# Diode_Drivers.net
KiCad netlist of a schematic drawn in Altium Designer
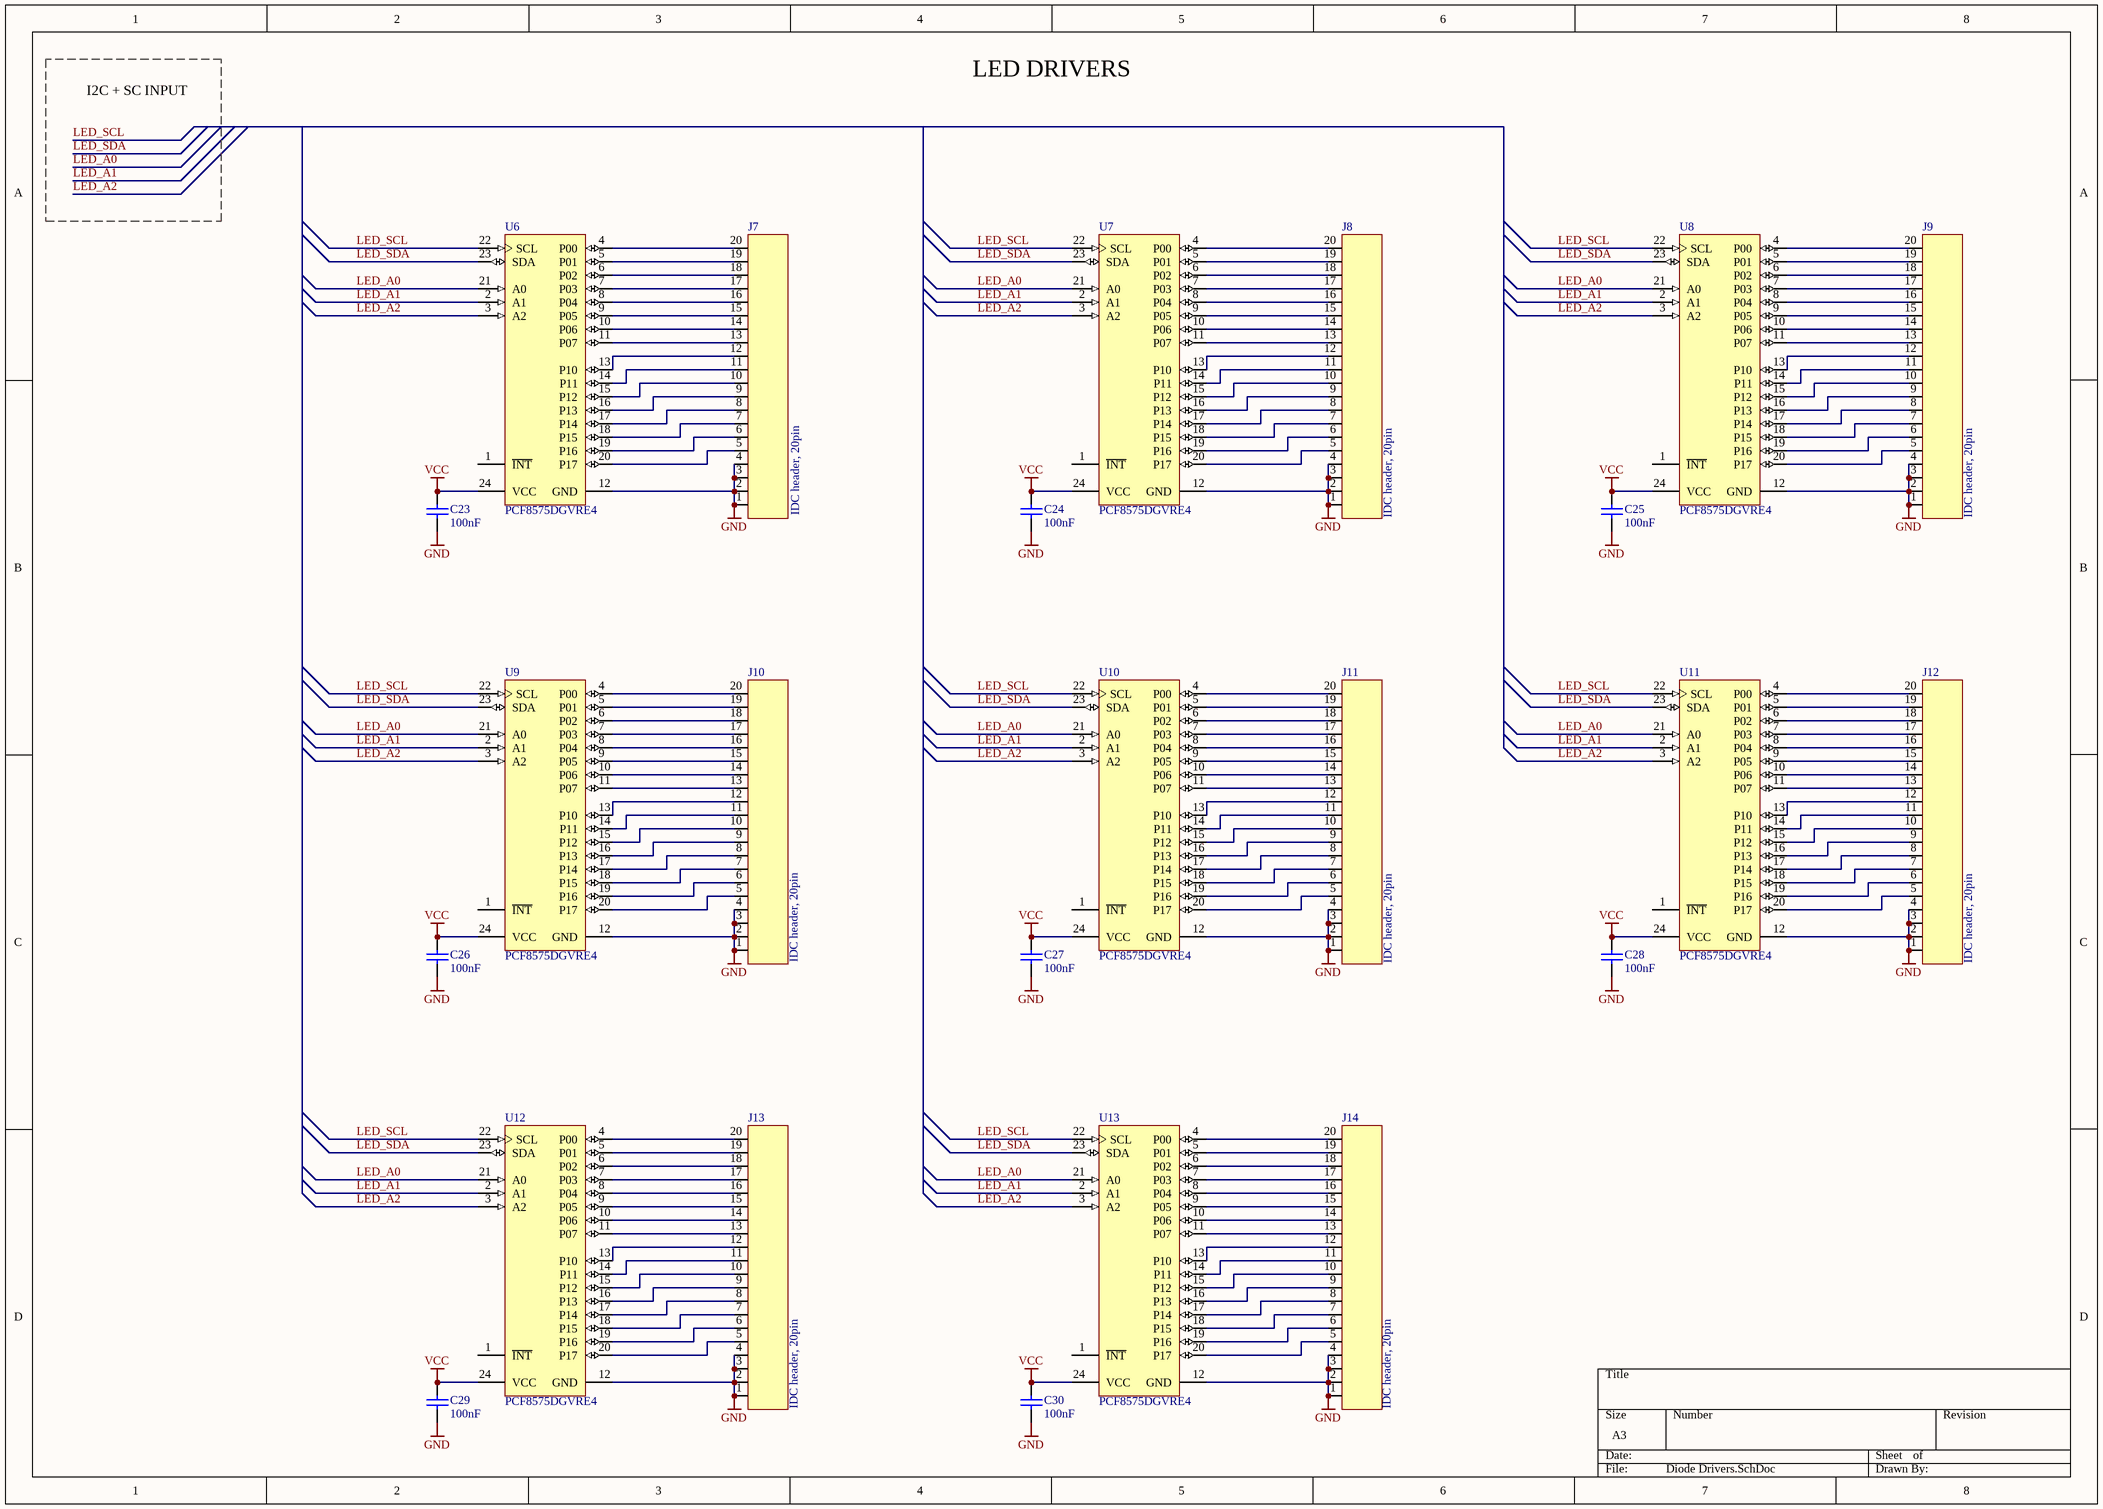
[diagram p0: Diode Drivers.SchDoc]

(export (version "E")
  (design (tool "Eeschema 10.0.6"))
  (components
    (comp (ref "C23")
      (value "100nF")
      (footprint "CAPC0603(1608)100_N")
      (description "CAP 100nF 25V ±20% 0603 (1608 Metric) Thickness 1mm SMD")
      (fields (field (name "TOLERANCE") "Â±20%") (field (name "Comment") "CAP 100nF 25V 0603(1608)"))
      (libsource (lib "Altium Content Vault") (part "CMP-1035-02589-1"))
    )
    (comp (ref "C24")
      (value "100nF")
      (footprint "CAPC0603(1608)100_N")
      (description "CAP 100nF 25V ±20% 0603 (1608 Metric) Thickness 1mm SMD")
      (fields (field (name "TOLERANCE") "Â±20%") (field (name "Comment") "CAP 100nF 25V 0603(1608)"))
      (libsource (lib "Altium Content Vault") (part "CMP-1035-02589-1"))
    )
    (comp (ref "C25")
      (value "100nF")
      (footprint "CAPC0603(1608)100_N")
      (description "CAP 100nF 25V ±20% 0603 (1608 Metric) Thickness 1mm SMD")
      (fields (field (name "TOLERANCE") "Â±20%") (field (name "Comment") "CAP 100nF 25V 0603(1608)"))
      (libsource (lib "Altium Content Vault") (part "CMP-1035-02589-1"))
    )
    (comp (ref "C26")
      (value "100nF")
      (footprint "CAPC0603(1608)100_N")
      (description "CAP 100nF 25V ±20% 0603 (1608 Metric) Thickness 1mm SMD")
      (fields (field (name "TOLERANCE") "Â±20%") (field (name "Comment") "CAP 100nF 25V 0603(1608)"))
      (libsource (lib "Altium Content Vault") (part "CMP-1035-02589-1"))
    )
    (comp (ref "C27")
      (value "100nF")
      (footprint "CAPC0603(1608)100_N")
      (description "CAP 100nF 25V ±20% 0603 (1608 Metric) Thickness 1mm SMD")
      (fields (field (name "TOLERANCE") "Â±20%") (field (name "Comment") "CAP 100nF 25V 0603(1608)"))
      (libsource (lib "Altium Content Vault") (part "CMP-1035-02589-1"))
    )
    (comp (ref "C28")
      (value "100nF")
      (footprint "CAPC0603(1608)100_N")
      (description "CAP 100nF 25V ±20% 0603 (1608 Metric) Thickness 1mm SMD")
      (fields (field (name "TOLERANCE") "Â±20%") (field (name "Comment") "CAP 100nF 25V 0603(1608)"))
      (libsource (lib "Altium Content Vault") (part "CMP-1035-02589-1"))
    )
    (comp (ref "C29")
      (value "100nF")
      (footprint "CAPC0603(1608)100_N")
      (description "CAP 100nF 25V ±20% 0603 (1608 Metric) Thickness 1mm SMD")
      (fields (field (name "TOLERANCE") "Â±20%") (field (name "Comment") "CAP 100nF 25V 0603(1608)"))
      (libsource (lib "Altium Content Vault") (part "CMP-1035-02589-1"))
    )
    (comp (ref "C30")
      (value "100nF")
      (footprint "CAPC0603(1608)100_N")
      (description "CAP 100nF 25V ±20% 0603 (1608 Metric) Thickness 1mm SMD")
      (fields (field (name "TOLERANCE") "Â±20%") (field (name "Comment") "CAP 100nF 25V 0603(1608)"))
      (libsource (lib "Altium Content Vault") (part "CMP-1035-02589-1"))
    )
    (comp (ref "J7")
      (value "IDC header, 20pin")
      (footprint "PKG_ZL231-20PG_R2.54-V")
      (description "Złącze IDC, męskie, proste, 20 pinów, na PCB")
      (libsource (lib "J") (part "J_ZL231-20PG_1"))
    )
    (comp (ref "J8")
      (value "IDC header, 20pin")
      (footprint "PKG_ZL231-20PG_R2.54-V")
      (description "Złącze IDC, męskie, proste, 20 pinów, na PCB")
      (libsource (lib "J") (part "J_ZL231-20PG_1"))
    )
    (comp (ref "J9")
      (value "IDC header, 20pin")
      (footprint "PKG_ZL231-20PG_R2.54-V")
      (libsource (lib "J") (part "J_ZL231-20PG_1"))
    )
    (comp (ref "J10")
      (value "IDC header, 20pin")
      (footprint "PKG_ZL231-20PG_R2.54-V")
      (description "Złącze IDC, męskie, proste, 20 pinów, na PCB")
      (libsource (lib "J") (part "J_ZL231-20PG_1"))
    )
    (comp (ref "J11")
      (value "IDC header, 20pin")
      (footprint "PKG_ZL231-20PG_R2.54-V")
      (description "Złącze IDC, męskie, proste, 20 pinów, na PCB")
      (libsource (lib "J") (part "J_ZL231-20PG_1"))
    )
    (comp (ref "J12")
      (value "IDC header, 20pin")
      (footprint "PKG_ZL231-20PG_R2.54-V")
      (description "Złącze IDC, męskie, proste, 20 pinów, na PCB")
      (libsource (lib "J") (part "J_ZL231-20PG_1"))
    )
    (comp (ref "J13")
      (value "IDC header, 20pin")
      (footprint "PKG_ZL231-20PG_R2.54-V")
      (description "Złącze IDC, męskie, proste, 20 pinów, na PCB")
      (libsource (lib "J") (part "J_ZL231-20PG_1"))
    )
    (comp (ref "J14")
      (value "IDC header, 20pin")
      (footprint "PKG_ZL231-20PG_R2.54-V")
      (description "Złącze IDC, męskie, proste, 20 pinów, na PCB")
      (libsource (lib "J") (part "J_ZL231-20PG_1"))
    )
    (comp (ref "U6")
      (value "PCF8575DGVRE4")
      (footprint "DGV24_M")
      (fields (field (name "MANUFACTURER") "Texas Instruments"))
      (libsource (lib "Altium Content Vault") (part "CMP-0314-00413-1"))
    )
    (comp (ref "U7")
      (value "PCF8575DGVRE4")
      (footprint "DGV24_M")
      (fields (field (name "MANUFACTURER") "Texas Instruments"))
      (libsource (lib "Altium Content Vault") (part "TI-PCF8575-TVSOP_DGV-24"))
    )
    (comp (ref "U8")
      (value "PCF8575DGVRE4")
      (footprint "DGV24_M")
      (fields (field (name "MANUFACTURER") "Texas Instruments"))
      (libsource (lib "Altium Content Vault") (part "TI-PCF8575-TVSOP_DGV-24"))
    )
    (comp (ref "U9")
      (value "PCF8575DGVRE4")
      (footprint "DGV24_M")
      (fields (field (name "MANUFACTURER") "Texas Instruments"))
      (libsource (lib "Altium Content Vault") (part "CMP-0314-00413-1"))
    )
    (comp (ref "U10")
      (value "PCF8575DGVRE4")
      (footprint "DGV24_M")
      (fields (field (name "MANUFACTURER") "Texas Instruments"))
      (libsource (lib "Altium Content Vault") (part "TI-PCF8575-TVSOP_DGV-24"))
    )
    (comp (ref "U11")
      (value "PCF8575DGVRE4")
      (footprint "DGV24_M")
      (fields (field (name "MANUFACTURER") "Texas Instruments"))
      (libsource (lib "Altium Content Vault") (part "TI-PCF8575-TVSOP_DGV-24"))
    )
    (comp (ref "U12")
      (value "PCF8575DGVRE4")
      (footprint "DGV24_M")
      (fields (field (name "MANUFACTURER") "Texas Instruments"))
      (libsource (lib "Altium Content Vault") (part "TI-PCF8575-TVSOP_DGV-24"))
    )
    (comp (ref "U13")
      (value "PCF8575DGVRE4")
      (footprint "DGV24_M")
      (fields (field (name "MANUFACTURER") "Texas Instruments"))
      (libsource (lib "Altium Content Vault") (part "TI-PCF8575-TVSOP_DGV-24"))
    )
  )
  (nets
    (net (code "1") (name "/LED_A0") (class "Default")
      (node (ref "U10") (pin "21") (pinfunction "A0_21") (pintype "input"))
      (node (ref "U11") (pin "21") (pinfunction "A0_21") (pintype "input"))
      (node (ref "U12") (pin "21") (pinfunction "A0_21") (pintype "input"))
      (node (ref "U13") (pin "21") (pinfunction "A0_21") (pintype "input"))
      (node (ref "U6") (pin "21") (pinfunction "A0_21") (pintype "input"))
      (node (ref "U7") (pin "21") (pinfunction "A0_21") (pintype "input"))
      (node (ref "U8") (pin "21") (pinfunction "A0_21") (pintype "input"))
      (node (ref "U9") (pin "21") (pinfunction "A0_21") (pintype "input"))
    )
    (net (code "2") (name "/LED_A1") (class "Default")
      (node (ref "U10") (pin "2") (pinfunction "A1_2") (pintype "input"))
      (node (ref "U11") (pin "2") (pinfunction "A1_2") (pintype "input"))
      (node (ref "U12") (pin "2") (pinfunction "A1_2") (pintype "input"))
      (node (ref "U13") (pin "2") (pinfunction "A1_2") (pintype "input"))
      (node (ref "U6") (pin "2") (pinfunction "A1_2") (pintype "input"))
      (node (ref "U7") (pin "2") (pinfunction "A1_2") (pintype "input"))
      (node (ref "U8") (pin "2") (pinfunction "A1_2") (pintype "input"))
      (node (ref "U9") (pin "2") (pinfunction "A1_2") (pintype "input"))
    )
    (net (code "3") (name "/LED_A2") (class "Default")
      (node (ref "U10") (pin "3") (pinfunction "A2_3") (pintype "input"))
      (node (ref "U11") (pin "3") (pinfunction "A2_3") (pintype "input"))
      (node (ref "U12") (pin "3") (pinfunction "A2_3") (pintype "input"))
      (node (ref "U13") (pin "3") (pinfunction "A2_3") (pintype "input"))
      (node (ref "U6") (pin "3") (pinfunction "A2_3") (pintype "input"))
      (node (ref "U7") (pin "3") (pinfunction "A2_3") (pintype "input"))
      (node (ref "U8") (pin "3") (pinfunction "A2_3") (pintype "input"))
      (node (ref "U9") (pin "3") (pinfunction "A2_3") (pintype "input"))
    )
    (net (code "4") (name "/LED_SCL") (class "Default")
      (node (ref "U10") (pin "22") (pinfunction "SCL_22") (pintype "input"))
      (node (ref "U11") (pin "22") (pinfunction "SCL_22") (pintype "input"))
      (node (ref "U12") (pin "22") (pinfunction "SCL_22") (pintype "input"))
      (node (ref "U13") (pin "22") (pinfunction "SCL_22") (pintype "input"))
      (node (ref "U6") (pin "22") (pinfunction "SCL_22") (pintype "input"))
      (node (ref "U7") (pin "22") (pinfunction "SCL_22") (pintype "input"))
      (node (ref "U8") (pin "22") (pinfunction "SCL_22") (pintype "input"))
      (node (ref "U9") (pin "22") (pinfunction "SCL_22") (pintype "input"))
    )
    (net (code "5") (name "/LED_SDA") (class "Default")
      (node (ref "U10") (pin "23") (pinfunction "SDA_23") (pintype "bidirectional"))
      (node (ref "U11") (pin "23") (pinfunction "SDA_23") (pintype "bidirectional"))
      (node (ref "U12") (pin "23") (pinfunction "SDA_23") (pintype "bidirectional"))
      (node (ref "U13") (pin "23") (pinfunction "SDA_23") (pintype "bidirectional"))
      (node (ref "U6") (pin "23") (pinfunction "SDA_23") (pintype "bidirectional"))
      (node (ref "U7") (pin "23") (pinfunction "SDA_23") (pintype "bidirectional"))
      (node (ref "U8") (pin "23") (pinfunction "SDA_23") (pintype "bidirectional"))
      (node (ref "U9") (pin "23") (pinfunction "SDA_23") (pintype "bidirectional"))
    )
    (net (code "6") (name "GND") (class "Default")
      (node (ref "C23") (pin "2") (pinfunction "2_2") (pintype "passive"))
      (node (ref "C24") (pin "2") (pinfunction "2_2") (pintype "passive"))
      (node (ref "C25") (pin "2") (pinfunction "2_2") (pintype "passive"))
      (node (ref "C26") (pin "2") (pinfunction "2_2") (pintype "passive"))
      (node (ref "C27") (pin "2") (pinfunction "2_2") (pintype "passive"))
      (node (ref "C28") (pin "2") (pinfunction "2_2") (pintype "passive"))
      (node (ref "C29") (pin "2") (pinfunction "2_2") (pintype "passive"))
      (node (ref "C30") (pin "2") (pinfunction "2_2") (pintype "passive"))
      (node (ref "J10") (pin "1") (pinfunction "1_1") (pintype "passive"))
      (node (ref "J10") (pin "2") (pinfunction "2_2") (pintype "passive"))
      (node (ref "J10") (pin "3") (pinfunction "3_3") (pintype "passive"))
      (node (ref "J10") (pin "4") (pinfunction "4_4") (pintype "passive"))
      (node (ref "J11") (pin "1") (pinfunction "1_1") (pintype "passive"))
      (node (ref "J11") (pin "2") (pinfunction "2_2") (pintype "passive"))
      (node (ref "J11") (pin "3") (pinfunction "3_3") (pintype "passive"))
      (node (ref "J11") (pin "4") (pinfunction "4_4") (pintype "passive"))
      (node (ref "J12") (pin "1") (pinfunction "1_1") (pintype "passive"))
      (node (ref "J12") (pin "2") (pinfunction "2_2") (pintype "passive"))
      (node (ref "J12") (pin "3") (pinfunction "3_3") (pintype "passive"))
      (node (ref "J12") (pin "4") (pinfunction "4_4") (pintype "passive"))
      (node (ref "J13") (pin "1") (pinfunction "1_1") (pintype "passive"))
      (node (ref "J13") (pin "2") (pinfunction "2_2") (pintype "passive"))
      (node (ref "J13") (pin "3") (pinfunction "3_3") (pintype "passive"))
      (node (ref "J13") (pin "4") (pinfunction "4_4") (pintype "passive"))
      (node (ref "J14") (pin "1") (pinfunction "1_1") (pintype "passive"))
      (node (ref "J14") (pin "2") (pinfunction "2_2") (pintype "passive"))
      (node (ref "J14") (pin "3") (pinfunction "3_3") (pintype "passive"))
      (node (ref "J14") (pin "4") (pinfunction "4_4") (pintype "passive"))
      (node (ref "J7") (pin "1") (pinfunction "1_1") (pintype "passive"))
      (node (ref "J7") (pin "2") (pinfunction "2_2") (pintype "passive"))
      (node (ref "J7") (pin "3") (pinfunction "3_3") (pintype "passive"))
      (node (ref "J7") (pin "4") (pinfunction "4_4") (pintype "passive"))
      (node (ref "J8") (pin "1") (pinfunction "1_1") (pintype "passive"))
      (node (ref "J8") (pin "2") (pinfunction "2_2") (pintype "passive"))
      (node (ref "J8") (pin "3") (pinfunction "3_3") (pintype "passive"))
      (node (ref "J8") (pin "4") (pinfunction "4_4") (pintype "passive"))
      (node (ref "J9") (pin "1") (pinfunction "1_1") (pintype "passive"))
      (node (ref "J9") (pin "2") (pinfunction "2_2") (pintype "passive"))
      (node (ref "J9") (pin "3") (pinfunction "3_3") (pintype "passive"))
      (node (ref "J9") (pin "4") (pinfunction "4_4") (pintype "passive"))
      (node (ref "U10") (pin "12") (pinfunction "GND_12") (pintype "power_in"))
      (node (ref "U11") (pin "12") (pinfunction "GND_12") (pintype "power_in"))
      (node (ref "U12") (pin "12") (pinfunction "GND_12") (pintype "power_in"))
      (node (ref "U13") (pin "12") (pinfunction "GND_12") (pintype "power_in"))
      (node (ref "U6") (pin "12") (pinfunction "GND_12") (pintype "power_in"))
      (node (ref "U7") (pin "12") (pinfunction "GND_12") (pintype "power_in"))
      (node (ref "U8") (pin "12") (pinfunction "GND_12") (pintype "power_in"))
      (node (ref "U9") (pin "12") (pinfunction "GND_12") (pintype "power_in"))
    )
    (net (code "7") (name "Net-(U6-P00)") (class "Default")
      (node (ref "J7") (pin "20") (pinfunction "20_20") (pintype "passive"))
      (node (ref "U6") (pin "4") (pinfunction "P00_4") (pintype "bidirectional"))
    )
    (net (code "8") (name "Net-(U6-P01)") (class "Default")
      (node (ref "J7") (pin "19") (pinfunction "19_19") (pintype "passive"))
      (node (ref "U6") (pin "5") (pinfunction "P01_5") (pintype "bidirectional"))
    )
    (net (code "9") (name "Net-(U6-P02)") (class "Default")
      (node (ref "J7") (pin "18") (pinfunction "18_18") (pintype "passive"))
      (node (ref "U6") (pin "6") (pinfunction "P02_6") (pintype "bidirectional"))
    )
    (net (code "10") (name "Net-(U6-P03)") (class "Default")
      (node (ref "J7") (pin "17") (pinfunction "17_17") (pintype "passive"))
      (node (ref "U6") (pin "7") (pinfunction "P03_7") (pintype "bidirectional"))
    )
    (net (code "11") (name "Net-(U6-P04)") (class "Default")
      (node (ref "J7") (pin "16") (pinfunction "16_16") (pintype "passive"))
      (node (ref "U6") (pin "8") (pinfunction "P04_8") (pintype "bidirectional"))
    )
    (net (code "12") (name "Net-(U6-P05)") (class "Default")
      (node (ref "J7") (pin "15") (pinfunction "15_15") (pintype "passive"))
      (node (ref "U6") (pin "9") (pinfunction "P05_9") (pintype "bidirectional"))
    )
    (net (code "13") (name "Net-(U6-P06)") (class "Default")
      (node (ref "J7") (pin "14") (pinfunction "14_14") (pintype "passive"))
      (node (ref "U6") (pin "10") (pinfunction "P06_10") (pintype "bidirectional"))
    )
    (net (code "14") (name "Net-(U6-P07)") (class "Default")
      (node (ref "J7") (pin "13") (pinfunction "13_13") (pintype "passive"))
      (node (ref "U6") (pin "11") (pinfunction "P07_11") (pintype "bidirectional"))
    )
    (net (code "15") (name "Net-(U6-P10)") (class "Default")
      (node (ref "J7") (pin "12") (pinfunction "12_12") (pintype "passive"))
      (node (ref "U6") (pin "13") (pinfunction "P10_13") (pintype "bidirectional"))
    )
    (net (code "16") (name "Net-(U6-P11)") (class "Default")
      (node (ref "J7") (pin "11") (pinfunction "11_11") (pintype "passive"))
      (node (ref "U6") (pin "14") (pinfunction "P11_14") (pintype "bidirectional"))
    )
    (net (code "17") (name "Net-(U6-P12)") (class "Default")
      (node (ref "J7") (pin "10") (pinfunction "10_10") (pintype "passive"))
      (node (ref "U6") (pin "15") (pinfunction "P12_15") (pintype "bidirectional"))
    )
    (net (code "18") (name "Net-(U6-P13)") (class "Default")
      (node (ref "J7") (pin "9") (pinfunction "9_9") (pintype "passive"))
      (node (ref "U6") (pin "16") (pinfunction "P13_16") (pintype "bidirectional"))
    )
    (net (code "19") (name "Net-(U6-P14)") (class "Default")
      (node (ref "J7") (pin "8") (pinfunction "8_8") (pintype "passive"))
      (node (ref "U6") (pin "17") (pinfunction "P14_17") (pintype "bidirectional"))
    )
    (net (code "20") (name "Net-(U6-P15)") (class "Default")
      (node (ref "J7") (pin "7") (pinfunction "7_7") (pintype "passive"))
      (node (ref "U6") (pin "18") (pinfunction "P15_18") (pintype "bidirectional"))
    )
    (net (code "21") (name "Net-(U6-P16)") (class "Default")
      (node (ref "J7") (pin "6") (pinfunction "6_6") (pintype "passive"))
      (node (ref "U6") (pin "19") (pinfunction "P16_19") (pintype "bidirectional"))
    )
    (net (code "22") (name "Net-(U6-P17)") (class "Default")
      (node (ref "J7") (pin "5") (pinfunction "5_5") (pintype "passive"))
      (node (ref "U6") (pin "20") (pinfunction "P17_20") (pintype "bidirectional"))
    )
    (net (code "23") (name "Net-(U7-P00)") (class "Default")
      (node (ref "J8") (pin "20") (pinfunction "20_20") (pintype "passive"))
      (node (ref "U7") (pin "4") (pinfunction "P00_4") (pintype "bidirectional"))
    )
    (net (code "24") (name "Net-(U7-P01)") (class "Default")
      (node (ref "J8") (pin "19") (pinfunction "19_19") (pintype "passive"))
      (node (ref "U7") (pin "5") (pinfunction "P01_5") (pintype "bidirectional"))
    )
    (net (code "25") (name "Net-(U7-P02)") (class "Default")
      (node (ref "J8") (pin "18") (pinfunction "18_18") (pintype "passive"))
      (node (ref "U7") (pin "6") (pinfunction "P02_6") (pintype "bidirectional"))
    )
    (net (code "26") (name "Net-(U7-P03)") (class "Default")
      (node (ref "J8") (pin "17") (pinfunction "17_17") (pintype "passive"))
      (node (ref "U7") (pin "7") (pinfunction "P03_7") (pintype "bidirectional"))
    )
    (net (code "27") (name "Net-(U7-P04)") (class "Default")
      (node (ref "J8") (pin "16") (pinfunction "16_16") (pintype "passive"))
      (node (ref "U7") (pin "8") (pinfunction "P04_8") (pintype "bidirectional"))
    )
    (net (code "28") (name "Net-(U7-P05)") (class "Default")
      (node (ref "J8") (pin "15") (pinfunction "15_15") (pintype "passive"))
      (node (ref "U7") (pin "9") (pinfunction "P05_9") (pintype "bidirectional"))
    )
    (net (code "29") (name "Net-(U7-P06)") (class "Default")
      (node (ref "J8") (pin "14") (pinfunction "14_14") (pintype "passive"))
      (node (ref "U7") (pin "10") (pinfunction "P06_10") (pintype "bidirectional"))
    )
    (net (code "30") (name "Net-(U7-P07)") (class "Default")
      (node (ref "J8") (pin "13") (pinfunction "13_13") (pintype "passive"))
      (node (ref "U7") (pin "11") (pinfunction "P07_11") (pintype "bidirectional"))
    )
    (net (code "31") (name "Net-(U7-P10)") (class "Default")
      (node (ref "J8") (pin "12") (pinfunction "12_12") (pintype "passive"))
      (node (ref "U7") (pin "13") (pinfunction "P10_13") (pintype "bidirectional"))
    )
    (net (code "32") (name "Net-(U7-P11)") (class "Default")
      (node (ref "J8") (pin "11") (pinfunction "11_11") (pintype "passive"))
      (node (ref "U7") (pin "14") (pinfunction "P11_14") (pintype "bidirectional"))
    )
    (net (code "33") (name "Net-(U7-P12)") (class "Default")
      (node (ref "J8") (pin "10") (pinfunction "10_10") (pintype "passive"))
      (node (ref "U7") (pin "15") (pinfunction "P12_15") (pintype "bidirectional"))
    )
    (net (code "34") (name "Net-(U7-P13)") (class "Default")
      (node (ref "J8") (pin "9") (pinfunction "9_9") (pintype "passive"))
      (node (ref "U7") (pin "16") (pinfunction "P13_16") (pintype "bidirectional"))
    )
    (net (code "35") (name "Net-(U7-P14)") (class "Default")
      (node (ref "J8") (pin "8") (pinfunction "8_8") (pintype "passive"))
      (node (ref "U7") (pin "17") (pinfunction "P14_17") (pintype "bidirectional"))
    )
    (net (code "36") (name "Net-(U7-P15)") (class "Default")
      (node (ref "J8") (pin "7") (pinfunction "7_7") (pintype "passive"))
      (node (ref "U7") (pin "18") (pinfunction "P15_18") (pintype "bidirectional"))
    )
    (net (code "37") (name "Net-(U7-P16)") (class "Default")
      (node (ref "J8") (pin "6") (pinfunction "6_6") (pintype "passive"))
      (node (ref "U7") (pin "19") (pinfunction "P16_19") (pintype "bidirectional"))
    )
    (net (code "38") (name "Net-(U7-P17)") (class "Default")
      (node (ref "J8") (pin "5") (pinfunction "5_5") (pintype "passive"))
      (node (ref "U7") (pin "20") (pinfunction "P17_20") (pintype "bidirectional"))
    )
    (net (code "39") (name "Net-(U8-P00)") (class "Default")
      (node (ref "J9") (pin "20") (pinfunction "20_20") (pintype "passive"))
      (node (ref "U8") (pin "4") (pinfunction "P00_4") (pintype "bidirectional"))
    )
    (net (code "40") (name "Net-(U8-P01)") (class "Default")
      (node (ref "J9") (pin "19") (pinfunction "19_19") (pintype "passive"))
      (node (ref "U8") (pin "5") (pinfunction "P01_5") (pintype "bidirectional"))
    )
    (net (code "41") (name "Net-(U8-P02)") (class "Default")
      (node (ref "J9") (pin "18") (pinfunction "18_18") (pintype "passive"))
      (node (ref "U8") (pin "6") (pinfunction "P02_6") (pintype "bidirectional"))
    )
    (net (code "42") (name "Net-(U8-P03)") (class "Default")
      (node (ref "J9") (pin "17") (pinfunction "17_17") (pintype "passive"))
      (node (ref "U8") (pin "7") (pinfunction "P03_7") (pintype "bidirectional"))
    )
    (net (code "43") (name "Net-(U8-P04)") (class "Default")
      (node (ref "J9") (pin "16") (pinfunction "16_16") (pintype "passive"))
      (node (ref "U8") (pin "8") (pinfunction "P04_8") (pintype "bidirectional"))
    )
    (net (code "44") (name "Net-(U8-P05)") (class "Default")
      (node (ref "J9") (pin "15") (pinfunction "15_15") (pintype "passive"))
      (node (ref "U8") (pin "9") (pinfunction "P05_9") (pintype "bidirectional"))
    )
    (net (code "45") (name "Net-(U8-P06)") (class "Default")
      (node (ref "J9") (pin "14") (pinfunction "14_14") (pintype "passive"))
      (node (ref "U8") (pin "10") (pinfunction "P06_10") (pintype "bidirectional"))
    )
    (net (code "46") (name "Net-(U8-P07)") (class "Default")
      (node (ref "J9") (pin "13") (pinfunction "13_13") (pintype "passive"))
      (node (ref "U8") (pin "11") (pinfunction "P07_11") (pintype "bidirectional"))
    )
    (net (code "47") (name "Net-(U8-P10)") (class "Default")
      (node (ref "J9") (pin "12") (pinfunction "12_12") (pintype "passive"))
      (node (ref "U8") (pin "13") (pinfunction "P10_13") (pintype "bidirectional"))
    )
    (net (code "48") (name "Net-(U8-P11)") (class "Default")
      (node (ref "J9") (pin "11") (pinfunction "11_11") (pintype "passive"))
      (node (ref "U8") (pin "14") (pinfunction "P11_14") (pintype "bidirectional"))
    )
    (net (code "49") (name "Net-(U8-P12)") (class "Default")
      (node (ref "J9") (pin "10") (pinfunction "10_10") (pintype "passive"))
      (node (ref "U8") (pin "15") (pinfunction "P12_15") (pintype "bidirectional"))
    )
    (net (code "50") (name "Net-(U8-P13)") (class "Default")
      (node (ref "J9") (pin "9") (pinfunction "9_9") (pintype "passive"))
      (node (ref "U8") (pin "16") (pinfunction "P13_16") (pintype "bidirectional"))
    )
    (net (code "51") (name "Net-(U8-P14)") (class "Default")
      (node (ref "J9") (pin "8") (pinfunction "8_8") (pintype "passive"))
      (node (ref "U8") (pin "17") (pinfunction "P14_17") (pintype "bidirectional"))
    )
    (net (code "52") (name "Net-(U8-P15)") (class "Default")
      (node (ref "J9") (pin "7") (pinfunction "7_7") (pintype "passive"))
      (node (ref "U8") (pin "18") (pinfunction "P15_18") (pintype "bidirectional"))
    )
    (net (code "53") (name "Net-(U8-P16)") (class "Default")
      (node (ref "J9") (pin "6") (pinfunction "6_6") (pintype "passive"))
      (node (ref "U8") (pin "19") (pinfunction "P16_19") (pintype "bidirectional"))
    )
    (net (code "54") (name "Net-(U8-P17)") (class "Default")
      (node (ref "J9") (pin "5") (pinfunction "5_5") (pintype "passive"))
      (node (ref "U8") (pin "20") (pinfunction "P17_20") (pintype "bidirectional"))
    )
    (net (code "55") (name "Net-(U9-P00)") (class "Default")
      (node (ref "J10") (pin "20") (pinfunction "20_20") (pintype "passive"))
      (node (ref "U9") (pin "4") (pinfunction "P00_4") (pintype "bidirectional"))
    )
    (net (code "56") (name "Net-(U9-P01)") (class "Default")
      (node (ref "J10") (pin "19") (pinfunction "19_19") (pintype "passive"))
      (node (ref "U9") (pin "5") (pinfunction "P01_5") (pintype "bidirectional"))
    )
    (net (code "57") (name "Net-(U9-P02)") (class "Default")
      (node (ref "J10") (pin "18") (pinfunction "18_18") (pintype "passive"))
      (node (ref "U9") (pin "6") (pinfunction "P02_6") (pintype "bidirectional"))
    )
    (net (code "58") (name "Net-(U9-P03)") (class "Default")
      (node (ref "J10") (pin "17") (pinfunction "17_17") (pintype "passive"))
      (node (ref "U9") (pin "7") (pinfunction "P03_7") (pintype "bidirectional"))
    )
    (net (code "59") (name "Net-(U9-P04)") (class "Default")
      (node (ref "J10") (pin "16") (pinfunction "16_16") (pintype "passive"))
      (node (ref "U9") (pin "8") (pinfunction "P04_8") (pintype "bidirectional"))
    )
    (net (code "60") (name "Net-(U9-P05)") (class "Default")
      (node (ref "J10") (pin "15") (pinfunction "15_15") (pintype "passive"))
      (node (ref "U9") (pin "9") (pinfunction "P05_9") (pintype "bidirectional"))
    )
    (net (code "61") (name "Net-(U9-P06)") (class "Default")
      (node (ref "J10") (pin "14") (pinfunction "14_14") (pintype "passive"))
      (node (ref "U9") (pin "10") (pinfunction "P06_10") (pintype "bidirectional"))
    )
    (net (code "62") (name "Net-(U9-P07)") (class "Default")
      (node (ref "J10") (pin "13") (pinfunction "13_13") (pintype "passive"))
      (node (ref "U9") (pin "11") (pinfunction "P07_11") (pintype "bidirectional"))
    )
    (net (code "63") (name "Net-(U9-P10)") (class "Default")
      (node (ref "J10") (pin "12") (pinfunction "12_12") (pintype "passive"))
      (node (ref "U9") (pin "13") (pinfunction "P10_13") (pintype "bidirectional"))
    )
    (net (code "64") (name "Net-(U9-P11)") (class "Default")
      (node (ref "J10") (pin "11") (pinfunction "11_11") (pintype "passive"))
      (node (ref "U9") (pin "14") (pinfunction "P11_14") (pintype "bidirectional"))
    )
    (net (code "65") (name "Net-(U9-P12)") (class "Default")
      (node (ref "J10") (pin "10") (pinfunction "10_10") (pintype "passive"))
      (node (ref "U9") (pin "15") (pinfunction "P12_15") (pintype "bidirectional"))
    )
    (net (code "66") (name "Net-(U9-P13)") (class "Default")
      (node (ref "J10") (pin "9") (pinfunction "9_9") (pintype "passive"))
      (node (ref "U9") (pin "16") (pinfunction "P13_16") (pintype "bidirectional"))
    )
    (net (code "67") (name "Net-(U9-P14)") (class "Default")
      (node (ref "J10") (pin "8") (pinfunction "8_8") (pintype "passive"))
      (node (ref "U9") (pin "17") (pinfunction "P14_17") (pintype "bidirectional"))
    )
    (net (code "68") (name "Net-(U9-P15)") (class "Default")
      (node (ref "J10") (pin "7") (pinfunction "7_7") (pintype "passive"))
      (node (ref "U9") (pin "18") (pinfunction "P15_18") (pintype "bidirectional"))
    )
    (net (code "69") (name "Net-(U9-P16)") (class "Default")
      (node (ref "J10") (pin "6") (pinfunction "6_6") (pintype "passive"))
      (node (ref "U9") (pin "19") (pinfunction "P16_19") (pintype "bidirectional"))
    )
    (net (code "70") (name "Net-(U9-P17)") (class "Default")
      (node (ref "J10") (pin "5") (pinfunction "5_5") (pintype "passive"))
      (node (ref "U9") (pin "20") (pinfunction "P17_20") (pintype "bidirectional"))
    )
    (net (code "71") (name "Net-(U10-P00)") (class "Default")
      (node (ref "J11") (pin "20") (pinfunction "20_20") (pintype "passive"))
      (node (ref "U10") (pin "4") (pinfunction "P00_4") (pintype "bidirectional"))
    )
    (net (code "72") (name "Net-(U10-P01)") (class "Default")
      (node (ref "J11") (pin "19") (pinfunction "19_19") (pintype "passive"))
      (node (ref "U10") (pin "5") (pinfunction "P01_5") (pintype "bidirectional"))
    )
    (net (code "73") (name "Net-(U10-P02)") (class "Default")
      (node (ref "J11") (pin "18") (pinfunction "18_18") (pintype "passive"))
      (node (ref "U10") (pin "6") (pinfunction "P02_6") (pintype "bidirectional"))
    )
    (net (code "74") (name "Net-(U10-P03)") (class "Default")
      (node (ref "J11") (pin "17") (pinfunction "17_17") (pintype "passive"))
      (node (ref "U10") (pin "7") (pinfunction "P03_7") (pintype "bidirectional"))
    )
    (net (code "75") (name "Net-(U10-P04)") (class "Default")
      (node (ref "J11") (pin "16") (pinfunction "16_16") (pintype "passive"))
      (node (ref "U10") (pin "8") (pinfunction "P04_8") (pintype "bidirectional"))
    )
    (net (code "76") (name "Net-(U10-P05)") (class "Default")
      (node (ref "J11") (pin "15") (pinfunction "15_15") (pintype "passive"))
      (node (ref "U10") (pin "9") (pinfunction "P05_9") (pintype "bidirectional"))
    )
    (net (code "77") (name "Net-(U10-P06)") (class "Default")
      (node (ref "J11") (pin "14") (pinfunction "14_14") (pintype "passive"))
      (node (ref "U10") (pin "10") (pinfunction "P06_10") (pintype "bidirectional"))
    )
    (net (code "78") (name "Net-(U10-P07)") (class "Default")
      (node (ref "J11") (pin "13") (pinfunction "13_13") (pintype "passive"))
      (node (ref "U10") (pin "11") (pinfunction "P07_11") (pintype "bidirectional"))
    )
    (net (code "79") (name "Net-(U10-P10)") (class "Default")
      (node (ref "J11") (pin "12") (pinfunction "12_12") (pintype "passive"))
      (node (ref "U10") (pin "13") (pinfunction "P10_13") (pintype "bidirectional"))
    )
    (net (code "80") (name "Net-(U10-P11)") (class "Default")
      (node (ref "J11") (pin "11") (pinfunction "11_11") (pintype "passive"))
      (node (ref "U10") (pin "14") (pinfunction "P11_14") (pintype "bidirectional"))
    )
    (net (code "81") (name "Net-(U10-P12)") (class "Default")
      (node (ref "J11") (pin "10") (pinfunction "10_10") (pintype "passive"))
      (node (ref "U10") (pin "15") (pinfunction "P12_15") (pintype "bidirectional"))
    )
    (net (code "82") (name "Net-(U10-P13)") (class "Default")
      (node (ref "J11") (pin "9") (pinfunction "9_9") (pintype "passive"))
      (node (ref "U10") (pin "16") (pinfunction "P13_16") (pintype "bidirectional"))
    )
    (net (code "83") (name "Net-(U10-P14)") (class "Default")
      (node (ref "J11") (pin "8") (pinfunction "8_8") (pintype "passive"))
      (node (ref "U10") (pin "17") (pinfunction "P14_17") (pintype "bidirectional"))
    )
    (net (code "84") (name "Net-(U10-P15)") (class "Default")
      (node (ref "J11") (pin "7") (pinfunction "7_7") (pintype "passive"))
      (node (ref "U10") (pin "18") (pinfunction "P15_18") (pintype "bidirectional"))
    )
    (net (code "85") (name "Net-(U10-P16)") (class "Default")
      (node (ref "J11") (pin "6") (pinfunction "6_6") (pintype "passive"))
      (node (ref "U10") (pin "19") (pinfunction "P16_19") (pintype "bidirectional"))
    )
    (net (code "86") (name "Net-(U10-P17)") (class "Default")
      (node (ref "J11") (pin "5") (pinfunction "5_5") (pintype "passive"))
      (node (ref "U10") (pin "20") (pinfunction "P17_20") (pintype "bidirectional"))
    )
    (net (code "87") (name "Net-(U11-P00)") (class "Default")
      (node (ref "J12") (pin "20") (pinfunction "20_20") (pintype "passive"))
      (node (ref "U11") (pin "4") (pinfunction "P00_4") (pintype "bidirectional"))
    )
    (net (code "88") (name "Net-(U11-P01)") (class "Default")
      (node (ref "J12") (pin "19") (pinfunction "19_19") (pintype "passive"))
      (node (ref "U11") (pin "5") (pinfunction "P01_5") (pintype "bidirectional"))
    )
    (net (code "89") (name "Net-(U11-P02)") (class "Default")
      (node (ref "J12") (pin "18") (pinfunction "18_18") (pintype "passive"))
      (node (ref "U11") (pin "6") (pinfunction "P02_6") (pintype "bidirectional"))
    )
    (net (code "90") (name "Net-(U11-P03)") (class "Default")
      (node (ref "J12") (pin "17") (pinfunction "17_17") (pintype "passive"))
      (node (ref "U11") (pin "7") (pinfunction "P03_7") (pintype "bidirectional"))
    )
    (net (code "91") (name "Net-(U11-P04)") (class "Default")
      (node (ref "J12") (pin "16") (pinfunction "16_16") (pintype "passive"))
      (node (ref "U11") (pin "8") (pinfunction "P04_8") (pintype "bidirectional"))
    )
    (net (code "92") (name "Net-(U11-P05)") (class "Default")
      (node (ref "J12") (pin "15") (pinfunction "15_15") (pintype "passive"))
      (node (ref "U11") (pin "9") (pinfunction "P05_9") (pintype "bidirectional"))
    )
    (net (code "93") (name "Net-(U11-P06)") (class "Default")
      (node (ref "J12") (pin "14") (pinfunction "14_14") (pintype "passive"))
      (node (ref "U11") (pin "10") (pinfunction "P06_10") (pintype "bidirectional"))
    )
    (net (code "94") (name "Net-(U11-P07)") (class "Default")
      (node (ref "J12") (pin "13") (pinfunction "13_13") (pintype "passive"))
      (node (ref "U11") (pin "11") (pinfunction "P07_11") (pintype "bidirectional"))
    )
    (net (code "95") (name "Net-(U11-P10)") (class "Default")
      (node (ref "J12") (pin "12") (pinfunction "12_12") (pintype "passive"))
      (node (ref "U11") (pin "13") (pinfunction "P10_13") (pintype "bidirectional"))
    )
    (net (code "96") (name "Net-(U11-P11)") (class "Default")
      (node (ref "J12") (pin "11") (pinfunction "11_11") (pintype "passive"))
      (node (ref "U11") (pin "14") (pinfunction "P11_14") (pintype "bidirectional"))
    )
    (net (code "97") (name "Net-(U11-P12)") (class "Default")
      (node (ref "J12") (pin "10") (pinfunction "10_10") (pintype "passive"))
      (node (ref "U11") (pin "15") (pinfunction "P12_15") (pintype "bidirectional"))
    )
    (net (code "98") (name "Net-(U11-P13)") (class "Default")
      (node (ref "J12") (pin "9") (pinfunction "9_9") (pintype "passive"))
      (node (ref "U11") (pin "16") (pinfunction "P13_16") (pintype "bidirectional"))
    )
    (net (code "99") (name "Net-(U11-P14)") (class "Default")
      (node (ref "J12") (pin "8") (pinfunction "8_8") (pintype "passive"))
      (node (ref "U11") (pin "17") (pinfunction "P14_17") (pintype "bidirectional"))
    )
    (net (code "100") (name "Net-(U11-P15)") (class "Default")
      (node (ref "J12") (pin "7") (pinfunction "7_7") (pintype "passive"))
      (node (ref "U11") (pin "18") (pinfunction "P15_18") (pintype "bidirectional"))
    )
    (net (code "101") (name "Net-(U11-P16)") (class "Default")
      (node (ref "J12") (pin "6") (pinfunction "6_6") (pintype "passive"))
      (node (ref "U11") (pin "19") (pinfunction "P16_19") (pintype "bidirectional"))
    )
    (net (code "102") (name "Net-(U11-P17)") (class "Default")
      (node (ref "J12") (pin "5") (pinfunction "5_5") (pintype "passive"))
      (node (ref "U11") (pin "20") (pinfunction "P17_20") (pintype "bidirectional"))
    )
    (net (code "103") (name "Net-(U12-P00)") (class "Default")
      (node (ref "J13") (pin "20") (pinfunction "20_20") (pintype "passive"))
      (node (ref "U12") (pin "4") (pinfunction "P00_4") (pintype "bidirectional"))
    )
    (net (code "104") (name "Net-(U12-P01)") (class "Default")
      (node (ref "J13") (pin "19") (pinfunction "19_19") (pintype "passive"))
      (node (ref "U12") (pin "5") (pinfunction "P01_5") (pintype "bidirectional"))
    )
    (net (code "105") (name "Net-(U12-P02)") (class "Default")
      (node (ref "J13") (pin "18") (pinfunction "18_18") (pintype "passive"))
      (node (ref "U12") (pin "6") (pinfunction "P02_6") (pintype "bidirectional"))
    )
    (net (code "106") (name "Net-(U12-P03)") (class "Default")
      (node (ref "J13") (pin "17") (pinfunction "17_17") (pintype "passive"))
      (node (ref "U12") (pin "7") (pinfunction "P03_7") (pintype "bidirectional"))
    )
    (net (code "107") (name "Net-(U12-P04)") (class "Default")
      (node (ref "J13") (pin "16") (pinfunction "16_16") (pintype "passive"))
      (node (ref "U12") (pin "8") (pinfunction "P04_8") (pintype "bidirectional"))
    )
    (net (code "108") (name "Net-(U12-P05)") (class "Default")
      (node (ref "J13") (pin "15") (pinfunction "15_15") (pintype "passive"))
      (node (ref "U12") (pin "9") (pinfunction "P05_9") (pintype "bidirectional"))
    )
    (net (code "109") (name "Net-(U12-P06)") (class "Default")
      (node (ref "J13") (pin "14") (pinfunction "14_14") (pintype "passive"))
      (node (ref "U12") (pin "10") (pinfunction "P06_10") (pintype "bidirectional"))
    )
    (net (code "110") (name "Net-(U12-P07)") (class "Default")
      (node (ref "J13") (pin "13") (pinfunction "13_13") (pintype "passive"))
      (node (ref "U12") (pin "11") (pinfunction "P07_11") (pintype "bidirectional"))
    )
    (net (code "111") (name "Net-(U12-P10)") (class "Default")
      (node (ref "J13") (pin "12") (pinfunction "12_12") (pintype "passive"))
      (node (ref "U12") (pin "13") (pinfunction "P10_13") (pintype "bidirectional"))
    )
    (net (code "112") (name "Net-(U12-P11)") (class "Default")
      (node (ref "J13") (pin "11") (pinfunction "11_11") (pintype "passive"))
      (node (ref "U12") (pin "14") (pinfunction "P11_14") (pintype "bidirectional"))
    )
    (net (code "113") (name "Net-(U12-P12)") (class "Default")
      (node (ref "J13") (pin "10") (pinfunction "10_10") (pintype "passive"))
      (node (ref "U12") (pin "15") (pinfunction "P12_15") (pintype "bidirectional"))
    )
    (net (code "114") (name "Net-(U12-P13)") (class "Default")
      (node (ref "J13") (pin "9") (pinfunction "9_9") (pintype "passive"))
      (node (ref "U12") (pin "16") (pinfunction "P13_16") (pintype "bidirectional"))
    )
    (net (code "115") (name "Net-(U12-P14)") (class "Default")
      (node (ref "J13") (pin "8") (pinfunction "8_8") (pintype "passive"))
      (node (ref "U12") (pin "17") (pinfunction "P14_17") (pintype "bidirectional"))
    )
    (net (code "116") (name "Net-(U12-P15)") (class "Default")
      (node (ref "J13") (pin "7") (pinfunction "7_7") (pintype "passive"))
      (node (ref "U12") (pin "18") (pinfunction "P15_18") (pintype "bidirectional"))
    )
    (net (code "117") (name "Net-(U12-P16)") (class "Default")
      (node (ref "J13") (pin "6") (pinfunction "6_6") (pintype "passive"))
      (node (ref "U12") (pin "19") (pinfunction "P16_19") (pintype "bidirectional"))
    )
    (net (code "118") (name "Net-(U12-P17)") (class "Default")
      (node (ref "J13") (pin "5") (pinfunction "5_5") (pintype "passive"))
      (node (ref "U12") (pin "20") (pinfunction "P17_20") (pintype "bidirectional"))
    )
    (net (code "119") (name "Net-(U13-P00)") (class "Default")
      (node (ref "J14") (pin "20") (pinfunction "20_20") (pintype "passive"))
      (node (ref "U13") (pin "4") (pinfunction "P00_4") (pintype "bidirectional"))
    )
    (net (code "120") (name "Net-(U13-P01)") (class "Default")
      (node (ref "J14") (pin "19") (pinfunction "19_19") (pintype "passive"))
      (node (ref "U13") (pin "5") (pinfunction "P01_5") (pintype "bidirectional"))
    )
    (net (code "121") (name "Net-(U13-P02)") (class "Default")
      (node (ref "J14") (pin "18") (pinfunction "18_18") (pintype "passive"))
      (node (ref "U13") (pin "6") (pinfunction "P02_6") (pintype "bidirectional"))
    )
    (net (code "122") (name "Net-(U13-P03)") (class "Default")
      (node (ref "J14") (pin "17") (pinfunction "17_17") (pintype "passive"))
      (node (ref "U13") (pin "7") (pinfunction "P03_7") (pintype "bidirectional"))
    )
    (net (code "123") (name "Net-(U13-P04)") (class "Default")
      (node (ref "J14") (pin "16") (pinfunction "16_16") (pintype "passive"))
      (node (ref "U13") (pin "8") (pinfunction "P04_8") (pintype "bidirectional"))
    )
    (net (code "124") (name "Net-(U13-P05)") (class "Default")
      (node (ref "J14") (pin "15") (pinfunction "15_15") (pintype "passive"))
      (node (ref "U13") (pin "9") (pinfunction "P05_9") (pintype "bidirectional"))
    )
    (net (code "125") (name "Net-(U13-P06)") (class "Default")
      (node (ref "J14") (pin "14") (pinfunction "14_14") (pintype "passive"))
      (node (ref "U13") (pin "10") (pinfunction "P06_10") (pintype "bidirectional"))
    )
    (net (code "126") (name "Net-(U13-P07)") (class "Default")
      (node (ref "J14") (pin "13") (pinfunction "13_13") (pintype "passive"))
      (node (ref "U13") (pin "11") (pinfunction "P07_11") (pintype "bidirectional"))
    )
    (net (code "127") (name "Net-(U13-P10)") (class "Default")
      (node (ref "J14") (pin "12") (pinfunction "12_12") (pintype "passive"))
      (node (ref "U13") (pin "13") (pinfunction "P10_13") (pintype "bidirectional"))
    )
    (net (code "128") (name "Net-(U13-P11)") (class "Default")
      (node (ref "J14") (pin "11") (pinfunction "11_11") (pintype "passive"))
      (node (ref "U13") (pin "14") (pinfunction "P11_14") (pintype "bidirectional"))
    )
    (net (code "129") (name "Net-(U13-P12)") (class "Default")
      (node (ref "J14") (pin "10") (pinfunction "10_10") (pintype "passive"))
      (node (ref "U13") (pin "15") (pinfunction "P12_15") (pintype "bidirectional"))
    )
    (net (code "130") (name "Net-(U13-P13)") (class "Default")
      (node (ref "J14") (pin "9") (pinfunction "9_9") (pintype "passive"))
      (node (ref "U13") (pin "16") (pinfunction "P13_16") (pintype "bidirectional"))
    )
    (net (code "131") (name "Net-(U13-P14)") (class "Default")
      (node (ref "J14") (pin "8") (pinfunction "8_8") (pintype "passive"))
      (node (ref "U13") (pin "17") (pinfunction "P14_17") (pintype "bidirectional"))
    )
    (net (code "132") (name "Net-(U13-P15)") (class "Default")
      (node (ref "J14") (pin "7") (pinfunction "7_7") (pintype "passive"))
      (node (ref "U13") (pin "18") (pinfunction "P15_18") (pintype "bidirectional"))
    )
    (net (code "133") (name "Net-(U13-P16)") (class "Default")
      (node (ref "J14") (pin "6") (pinfunction "6_6") (pintype "passive"))
      (node (ref "U13") (pin "19") (pinfunction "P16_19") (pintype "bidirectional"))
    )
    (net (code "134") (name "Net-(U13-P17)") (class "Default")
      (node (ref "J14") (pin "5") (pinfunction "5_5") (pintype "passive"))
      (node (ref "U13") (pin "20") (pinfunction "P17_20") (pintype "bidirectional"))
    )
    (net (code "135") (name "VCC") (class "Default")
      (node (ref "C23") (pin "1") (pinfunction "1_1") (pintype "passive"))
      (node (ref "C24") (pin "1") (pinfunction "1_1") (pintype "passive"))
      (node (ref "C25") (pin "1") (pinfunction "1_1") (pintype "passive"))
      (node (ref "C26") (pin "1") (pinfunction "1_1") (pintype "passive"))
      (node (ref "C27") (pin "1") (pinfunction "1_1") (pintype "passive"))
      (node (ref "C28") (pin "1") (pinfunction "1_1") (pintype "passive"))
      (node (ref "C29") (pin "1") (pinfunction "1_1") (pintype "passive"))
      (node (ref "C30") (pin "1") (pinfunction "1_1") (pintype "passive"))
      (node (ref "U10") (pin "24") (pinfunction "VCC_24") (pintype "power_in"))
      (node (ref "U11") (pin "24") (pinfunction "VCC_24") (pintype "power_in"))
      (node (ref "U12") (pin "24") (pinfunction "VCC_24") (pintype "power_in"))
      (node (ref "U13") (pin "24") (pinfunction "VCC_24") (pintype "power_in"))
      (node (ref "U6") (pin "24") (pinfunction "VCC_24") (pintype "power_in"))
      (node (ref "U7") (pin "24") (pinfunction "VCC_24") (pintype "power_in"))
      (node (ref "U8") (pin "24") (pinfunction "VCC_24") (pintype "power_in"))
      (node (ref "U9") (pin "24") (pinfunction "VCC_24") (pintype "power_in"))
    )
    (net (code "136") (name "unconnected-(U6-~{INT}-Pad1)") (class "Default")
      (node (ref "U6") (pin "1") (pinfunction "~{INT}_1") (pintype "open_collector"))
    )
    (net (code "137") (name "unconnected-(U7-~{INT}-Pad1)") (class "Default")
      (node (ref "U7") (pin "1") (pinfunction "~{INT}_1") (pintype "open_collector"))
    )
    (net (code "138") (name "unconnected-(U8-~{INT}-Pad1)") (class "Default")
      (node (ref "U8") (pin "1") (pinfunction "~{INT}_1") (pintype "open_collector"))
    )
    (net (code "139") (name "unconnected-(U9-~{INT}-Pad1)") (class "Default")
      (node (ref "U9") (pin "1") (pinfunction "~{INT}_1") (pintype "open_collector"))
    )
    (net (code "140") (name "unconnected-(U10-~{INT}-Pad1)") (class "Default")
      (node (ref "U10") (pin "1") (pinfunction "~{INT}_1") (pintype "open_collector"))
    )
    (net (code "141") (name "unconnected-(U11-~{INT}-Pad1)") (class "Default")
      (node (ref "U11") (pin "1") (pinfunction "~{INT}_1") (pintype "open_collector"))
    )
    (net (code "142") (name "unconnected-(U12-~{INT}-Pad1)") (class "Default")
      (node (ref "U12") (pin "1") (pinfunction "~{INT}_1") (pintype "open_collector"))
    )
    (net (code "143") (name "unconnected-(U13-~{INT}-Pad1)") (class "Default")
      (node (ref "U13") (pin "1") (pinfunction "~{INT}_1") (pintype "open_collector"))
    )
  )
)
